# Power.net
KiCad netlist of a schematic drawn in Altium Designer
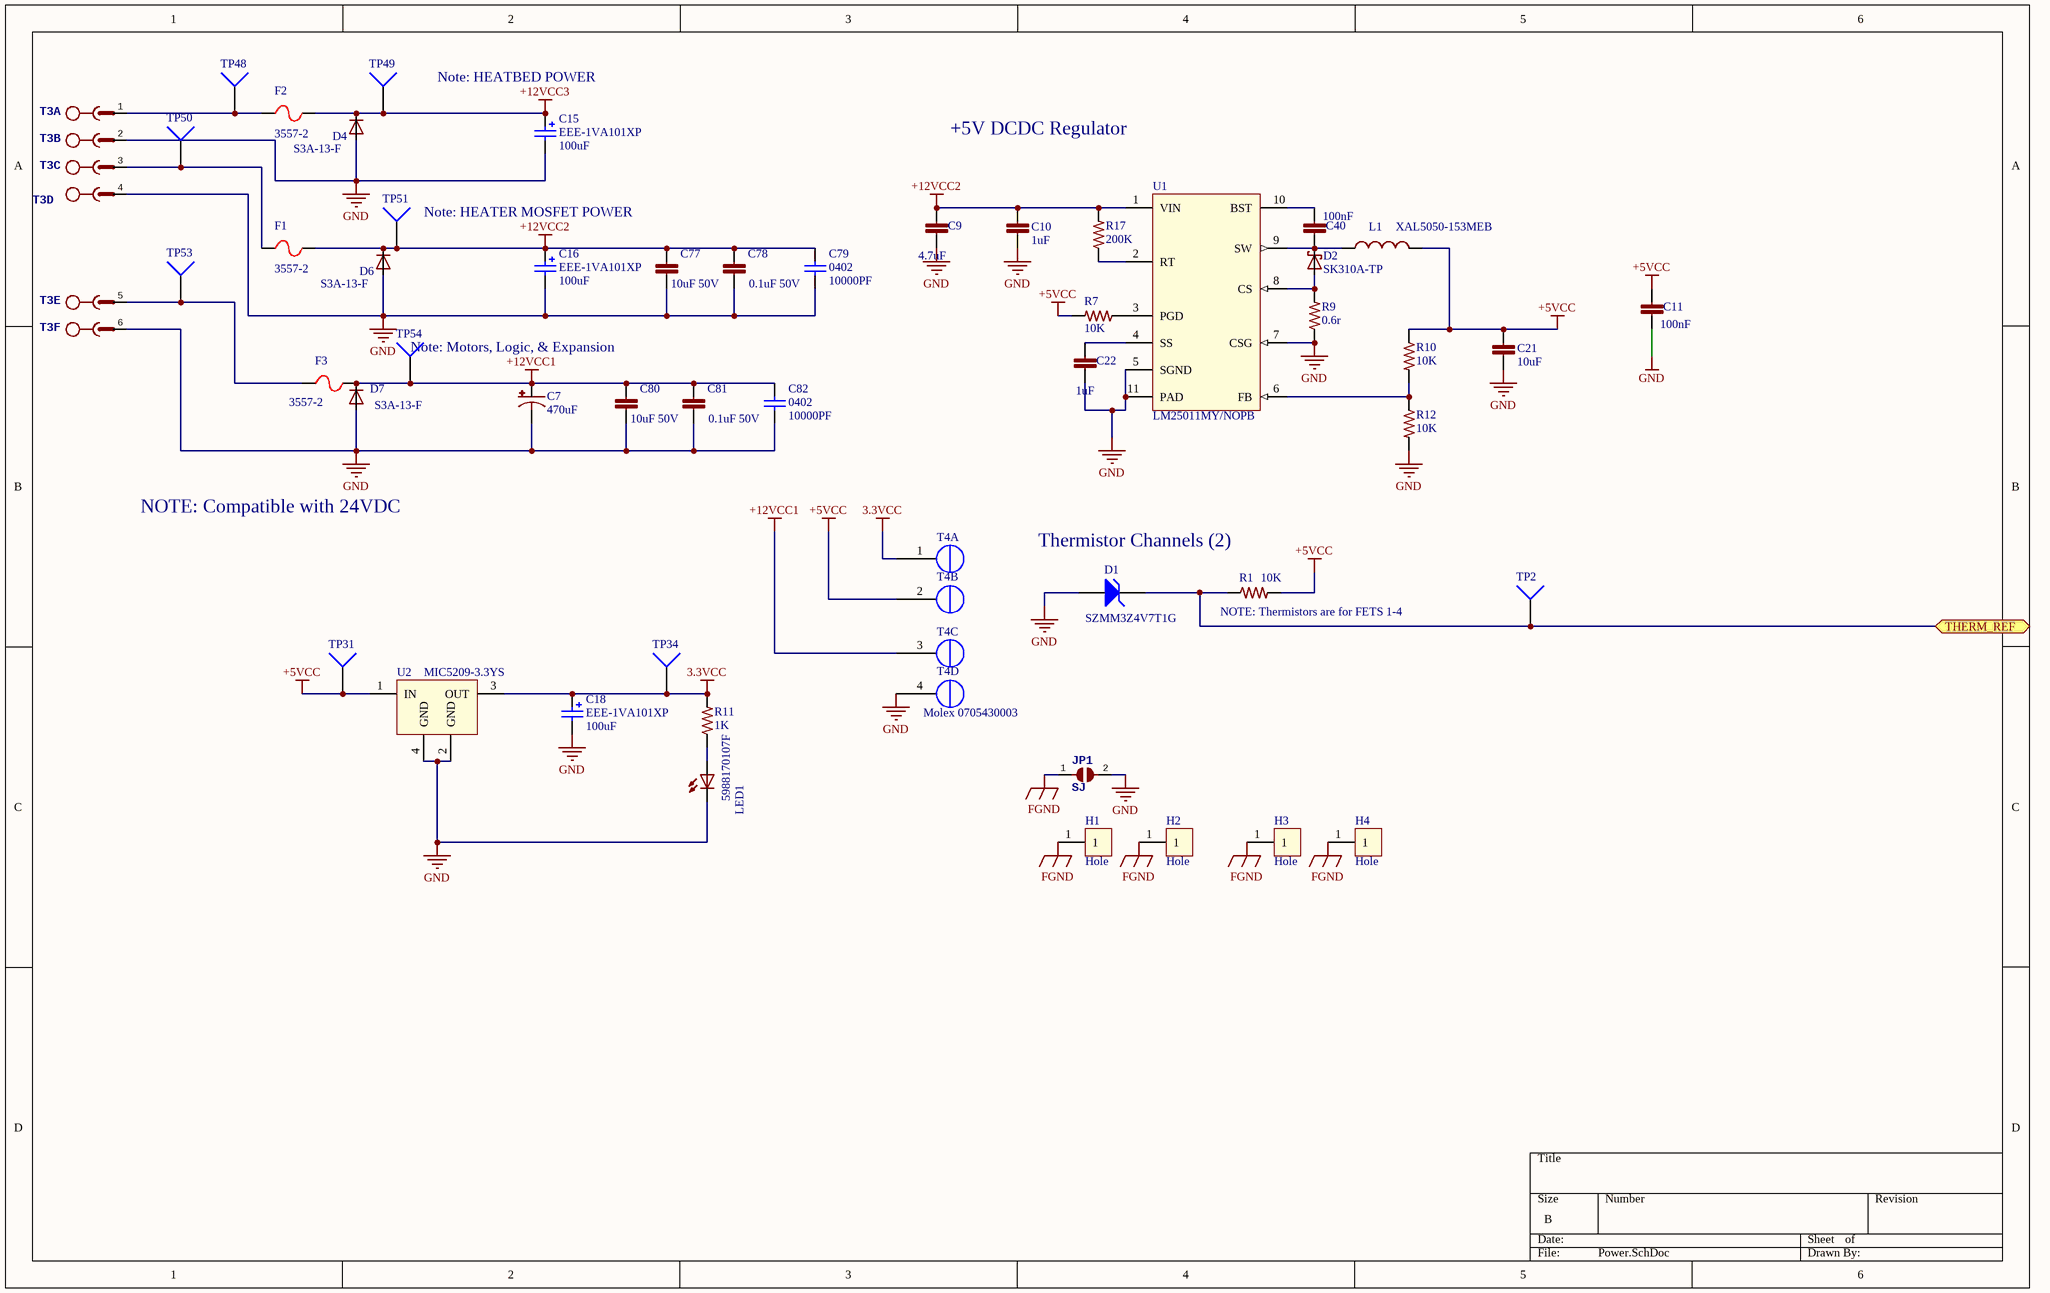
[diagram p0: Power.SchDoc]

(export (version "E")
  (design (tool "Eeschema 10.0.6"))
  (components
    (comp (ref "C7")
      (value "470uF")
      (footprint "C12,5-5")
      (description "CAP ALU 470uF 50V 20%")
      (fields
        (field (name "MANUFACTURERPARTNUMBER") "UPW1H471MHD1TO")
        (field (name "PUBLISHER") "UltiMachine")
      )
      (libsource (lib "Tigershark3D") (part "UPW1H471MHD1TO"))
    )
    (comp (ref "C9")
      (value "4.7uF")
      (footprint "C1206")
      (description "CAP CER 1206 4.7uF 50V 10% X5R")
      (fields
        (field (name "MANUFACTURERPARTNUMBER") "C1206C475K5PACTU")
        (field (name "PUBLISHER") "UltiMachine")
      )
      (libsource (lib "3Delight") (part "C1206C475K5PACTU"))
    )
    (comp (ref "C10")
      (value "1uF")
      (footprint "C0805")
      (description "CAP CER 0805 1uF 50V 10% X7R")
      (fields
        (field (name "MANUFACTURERPARTNUMBER") "GRM21BR71H105KA12L")
        (field (name "PUBLISHER") "UltiMachine")
      )
      (libsource (lib "3Delight") (part "GRM21BR71H105KA12L"))
    )
    (comp (ref "C11")
      (value "100nF")
      (footprint "C0603")
      (description "CAP CER 0603 100nF 50V 10% X7R")
      (fields
        (field (name "MANUFACTURERPARTNUMBER") "C0603C104K5RACTU")
        (field (name "PUBLISHER") "UltiMachine")
      )
      (libsource (lib "3Delight") (part "C0603C104K5RACTU"))
    )
    (comp (ref "C15")
      (value "EEE-1VA101XP")
      (footprint "EEE-1VA101XP")
      (description "CAP ALUM 100UF 35V 20% SMD")
      (fields (field (name "DIGIKEY PART #") "PCE3951CT-ND") (field (name "ALTIUM_VALUE") "100uF"))
      (libsource (lib "Tigershark3D") (part "EEE-1VA101XP"))
    )
    (comp (ref "C16")
      (value "EEE-1VA101XP")
      (footprint "EEE-1VA101XP")
      (description "CAP ALUM 100UF 35V 20% SMD")
      (fields (field (name "DIGIKEY PART #") "PCE3951CT-ND") (field (name "ALTIUM_VALUE") "100uF"))
      (libsource (lib "Tigershark3D") (part "EEE-1VA101XP"))
    )
    (comp (ref "C18")
      (value "EEE-1VA101XP")
      (footprint "EEE-1VA101XP")
      (description "CAP ALUM 100UF 35V 20% SMD")
      (fields (field (name "DIGIKEY PART #") "PCE3951CT-ND") (field (name "ALTIUM_VALUE") "100uF"))
      (libsource (lib "Tigershark3D") (part "EEE-1VA101XP"))
    )
    (comp (ref "C21")
      (value "10uF")
      (footprint "C0805")
      (description "CAP CER 0805 10uF 10V 10% X5R")
      (fields
        (field (name "MANUFACTURERPARTNUMBER") "C0805C106K8PACTU")
        (field (name "PUBLISHER") "UltiMachine")
      )
      (libsource (lib "3Delight") (part "C0805C106K8PACTU"))
    )
    (comp (ref "C22")
      (value "1uF")
      (footprint "C0402")
      (description "CAP CER 0402 1uF 6.3V 10% X5R")
      (fields
        (field (name "MANUFACTURERPARTNUMBER") "GRM155R60J105KE19D")
        (field (name "PUBLISHER") "UltiMachine")
      )
      (libsource (lib "3Delight") (part "GRM155R60J105KE19D"))
    )
    (comp (ref "C40")
      (value "100nF")
      (footprint "C0603")
      (description "CAP CER 0603 100nF 50V 10% X7R")
      (fields
        (field (name "MANUFACTURERPARTNUMBER") "C0603C104K5RACTU")
        (field (name "PUBLISHER") "UltiMachine")
      )
      (libsource (lib "3Delight") (part "C0603C104K5RACTU"))
    )
    (comp (ref "C77")
      (value "10uF 50V")
      (footprint "C1206")
      (description "CAP CER 10UF 50V 10% X5R 1206")
      (fields
        (field (name "MANUFACTURER") "Samsung")
        (field (name "MANUFACTURERPARTNUMBER") "CL31A106KBHNNNE")
        (field (name "PUBLISHER") "UltiMachine")
      )
      (libsource (lib "Tigershark3D") (part "CL31A106KBHNNNE"))
    )
    (comp (ref "C78")
      (value "0.1uF 50V")
      (footprint "C0603")
      (description "CAP CER 0.1UF 50V 10% X7R 0603")
      (fields
        (field (name "MANUFACTURERPARTNUMBER") "CL10B104KB8SFNC")
        (field (name "PUBLISHER") "UltiMachine")
      )
      (libsource (lib "Tigershark3D") (part "CL10B104KB8SFNC"))
    )
    (comp (ref "C79")
      (value "10000PF")
      (footprint "C0402")
      (description "CAP CER 10000PF 50V 5% X7R 0402")
      (fields
        (field (name "MANUFACTURE PART #") "CL05B103JB5NNNC")
        (field (name "MANUFACTURER") "Samsung")
        (field (name "PACKAGEREFERENCE") "0402")
        (field (name "PUBLISHER") "Ultimachine")
      )
      (libsource (lib "Tigershark3D") (part "CL05B103JB5NNNC"))
    )
    (comp (ref "C80")
      (value "10uF 50V")
      (footprint "C1206")
      (description "CAP CER 10UF 50V 10% X5R 1206")
      (fields
        (field (name "MANUFACTURER") "Samsung")
        (field (name "MANUFACTURERPARTNUMBER") "CL31A106KBHNNNE")
        (field (name "PUBLISHER") "UltiMachine")
      )
      (libsource (lib "Tigershark3D") (part "CL31A106KBHNNNE"))
    )
    (comp (ref "C81")
      (value "0.1uF 50V")
      (footprint "C0603")
      (description "CAP CER 0.1UF 50V 10% X7R 0603")
      (fields
        (field (name "MANUFACTURERPARTNUMBER") "CL10B104KB8SFNC")
        (field (name "PUBLISHER") "UltiMachine")
      )
      (libsource (lib "Tigershark3D") (part "CL10B104KB8SFNC"))
    )
    (comp (ref "C82")
      (value "10000PF")
      (footprint "C0402")
      (description "CAP CER 10000PF 50V 5% X7R 0402")
      (fields
        (field (name "MANUFACTURE PART #") "CL05B103JB5NNNC")
        (field (name "MANUFACTURER") "Samsung")
        (field (name "PACKAGEREFERENCE") "0402")
        (field (name "PUBLISHER") "Ultimachine")
      )
      (libsource (lib "Tigershark3D") (part "CL05B103JB5NNNC"))
    )
    (comp (ref "D1")
      (value "SZMM3Z4V7T1G")
      (footprint "SZMM3Z4V7T1G")
      (description "Zener Diode")
      (fields (field (name "PUBLISHER") "Altium Limited"))
      (libsource (lib "Miscellaneous Devices") (part "D Zener"))
    )
    (comp (ref "D2")
      (value "SK310A-TP")
      (footprint "SMA-SM")
      (description "DIODE Schottky 3A SMA")
      (fields (field (name "MANUFACTURERPARTNUMBER") "SK310A") (field (name "PUBLISHER") "UltiMachine"))
      (libsource (lib "3Delight") (part "SK310A"))
    )
    (comp (ref "D4")
      (value "S3A-13-F")
      (footprint "DO-214AB")
      (description "DIODE DO-214AB")
      (fields (field (name "PUBLISHER") "UltiMachine"))
      (libsource (lib "3Delight") (part "S3A-13-F"))
    )
    (comp (ref "D6")
      (value "S3A-13-F")
      (footprint "DO-214AB")
      (description "DIODE DO-214AB")
      (fields (field (name "PUBLISHER") "UltiMachine"))
      (libsource (lib "3Delight") (part "S3A-13-F"))
    )
    (comp (ref "D7")
      (value "S3A-13-F")
      (footprint "DO-214AB")
      (description "DIODE DO-214AB")
      (fields (field (name "PUBLISHER") "UltiMachine"))
      (libsource (lib "3Delight") (part "S3A-13-F"))
    )
    (comp (ref "F1")
      (value "3557-2")
      (footprint "3557")
      (description "FUSE PTH ATO")
      (fields (field (name "PUBLISHER") "UltiMachine"))
      (libsource (lib "3Delight") (part "3557-2"))
    )
    (comp (ref "F2")
      (value "3557-2")
      (footprint "3557")
      (description "FUSE PTH ATO")
      (fields (field (name "PUBLISHER") "UltiMachine"))
      (libsource (lib "3Delight") (part "3557-2"))
    )
    (comp (ref "F3")
      (value "3557-2")
      (footprint "3557")
      (description "FUSE PTH ATO")
      (fields (field (name "PUBLISHER") "UltiMachine"))
      (libsource (lib "3Delight") (part "3557-2"))
    )
    (comp (ref "H1")
      (value "Hole")
      (footprint "Wave_hole_3x7-singleSided")
      (libsource (lib "3Delight") (part "Hole"))
    )
    (comp (ref "H2")
      (value "Hole")
      (footprint "Wave_hole_3x7-singleSided")
      (libsource (lib "3Delight") (part "Hole"))
    )
    (comp (ref "H3")
      (value "Hole")
      (footprint "Wave_hole_3x7-singleSided")
      (libsource (lib "3Delight") (part "Hole"))
    )
    (comp (ref "H4")
      (value "Hole")
      (footprint "Wave_hole_3x7-singleSided")
      (libsource (lib "3Delight") (part "Hole"))
    )
    (comp (ref "JP1")
      (value "SJ")
      (footprint "SJ")
      (description "SMD solder jumper")
      (fields (field (name "PUBLISHER") "UltiMachine"))
      (libsource (lib "3Delight") (part "SJ"))
    )
    (comp (ref "L1")
      (value "XAL5050-153MEB")
      (footprint "XAL50xx-153")
      (description "IND 15uH 3.9A 20%")
      (fields (field (name "PUBLISHER") "UltiMachine"))
      (libsource (lib "3Delight") (part "XAL5050-153MEB"))
    )
    (comp (ref "LED1")
      (value "5988170107F")
      (footprint "LED2012120")
      (description "LED 0805 Green")
      (fields (field (name "PUBLISHER") "UltiMachine"))
      (libsource (lib "3Delight") (part "5988170107F"))
    )
    (comp (ref "R1")
      (value "10K")
      (footprint "R0603")
      (description "RES 0603 10K 100mW 1%")
      (fields
        (field (name "MANUFACTURERPARTNUMBER") "ERJ-3EKF1002V")
        (field (name "PUBLISHER") "UltiMachine")
      )
      (libsource (lib "3Delight") (part "ERJ-3EKF1002V"))
    )
    (comp (ref "R7")
      (value "10K")
      (footprint "R0603")
      (description "RES 0603 10K 100mW 1%")
      (fields
        (field (name "MANUFACTURERPARTNUMBER") "ERJ-3EKF1002V")
        (field (name "PUBLISHER") "UltiMachine")
      )
      (libsource (lib "3Delight") (part "ERJ-3EKF1002V"))
    )
    (comp (ref "R9")
      (value "0.6r")
      (footprint "2512R-0.55")
      (description "RES 0.06 OHM 1W 1% 2512 SMD")
      (fields
        (field (name "MANUFACTURERPARTNUMBER") "RL2512FK-070R06L")
        (field (name "PUBLISHER") "UltiMachine")
      )
      (libsource (lib "3Delight") (part "RL2512FK-070R06L"))
    )
    (comp (ref "R10")
      (value "10K")
      (footprint "R0603")
      (description "RES 0603 10K 100mW 1%")
      (fields
        (field (name "MANUFACTURERPARTNUMBER") "ERJ-3EKF1002V")
        (field (name "PUBLISHER") "UltiMachine")
      )
      (libsource (lib "3Delight") (part "ERJ-3EKF1002V"))
    )
    (comp (ref "R11")
      (value "1K")
      (footprint "R0603")
      (description "RES 0603 1K 100mW 1%")
      (fields
        (field (name "MANUFACTURERPARTNUMBER") "ERJ-3EKF1001V")
        (field (name "PUBLISHER") "UltiMachine")
      )
      (libsource (lib "Tigershark3D") (part "ERJ-3EKF1001V"))
    )
    (comp (ref "R12")
      (value "10K")
      (footprint "R0603")
      (description "RES 0603 10K 100mW 1%")
      (fields
        (field (name "MANUFACTURERPARTNUMBER") "ERJ-3EKF1002V")
        (field (name "PUBLISHER") "UltiMachine")
      )
      (libsource (lib "3Delight") (part "ERJ-3EKF1002V"))
    )
    (comp (ref "R17")
      (value "200K")
      (footprint "R0402")
      (description "RES 0402 22r 63mW 1%")
      (fields
        (field (name "MANUFACTURERPARTNUMBER") "CRCW0402200KFKED")
        (field (name "PUBLISHER") "UltiMachine")
      )
      (libsource (lib "3Delight") (part "CRCW0402200KFKED"))
    )
    (comp (ref "T3")
      (value "MSTBV6")
      (footprint "MSTBV6")
      (description "PHOENIX")
      (fields (field (name "PUBLISHER") "UltiMachine"))
      (libsource (lib "3Delight") (part "MSTBV6"))
    )
    (comp (ref "T4")
      (value "Molex 0705430003")
      (footprint "4POL254")
      (description "Molex 4 Pin Clip Connector")
      (libsource (lib "ZMBo Schematic Library") (part "Molex 0705430003 Alt"))
    )
    (comp (ref "TP2")
      (value "TP4")
      (footprint "TP-2")
      (description "Socket")
      (fields (field (name "PUBLISHER") "Altium Limited"))
      (libsource (lib "ZMBo Schematic Library") (part "Socket"))
    )
    (comp (ref "TP31")
      (value "TP4")
      (footprint "TP-2")
      (description "Socket")
      (fields (field (name "PUBLISHER") "Altium Limited"))
      (libsource (lib "ZMBo Schematic Library") (part "Socket"))
    )
    (comp (ref "TP34")
      (value "TP4")
      (footprint "TP-2")
      (description "Socket")
      (fields (field (name "PUBLISHER") "Altium Limited"))
      (libsource (lib "ZMBo Schematic Library") (part "Socket"))
    )
    (comp (ref "TP48")
      (value "TP4")
      (footprint "TP-2")
      (description "Socket")
      (fields (field (name "PUBLISHER") "Altium Limited"))
      (libsource (lib "ZMBo Schematic Library") (part "Socket"))
    )
    (comp (ref "TP49")
      (value "TP4")
      (footprint "TP-2")
      (description "Socket")
      (fields (field (name "PUBLISHER") "Altium Limited"))
      (libsource (lib "ZMBo Schematic Library") (part "Socket"))
    )
    (comp (ref "TP50")
      (value "TP4")
      (footprint "TP-2")
      (description "Socket")
      (fields (field (name "PUBLISHER") "Altium Limited"))
      (libsource (lib "ZMBo Schematic Library") (part "Socket"))
    )
    (comp (ref "TP51")
      (value "TP4")
      (footprint "TP-2")
      (description "Socket")
      (fields (field (name "PUBLISHER") "Altium Limited"))
      (libsource (lib "ZMBo Schematic Library") (part "Socket"))
    )
    (comp (ref "TP53")
      (value "TP4")
      (footprint "TP-2")
      (description "Socket")
      (fields (field (name "PUBLISHER") "Altium Limited"))
      (libsource (lib "ZMBo Schematic Library") (part "Socket"))
    )
    (comp (ref "TP54")
      (value "TP4")
      (footprint "TP-2")
      (description "Socket")
      (fields (field (name "PUBLISHER") "Altium Limited"))
      (libsource (lib "ZMBo Schematic Library") (part "Socket"))
    )
    (comp (ref "U1")
      (value "LM25011MY/NOPB")
      (footprint "VSSOP10")
      (description "REG BUCK")
      (libsource (lib "3Delight") (part "LM25011"))
    )
    (comp (ref "U2")
      (value "MIC5209-3.3YS")
      (footprint "SOT230P700X190-4N")
      (libsource (lib "3Delight") (part "MIC5209-3.3YS"))
    )
  )
  (nets
    (net (code "1") (name "+5VCC") (class "Default")
      (node (ref "C11") (pin "1") (pinfunction "1_1") (pintype "passive"))
      (node (ref "C21") (pin "1") (pinfunction "1_1") (pintype "passive"))
      (node (ref "L1") (pin "2") (pinfunction "2_2") (pintype "passive"))
      (node (ref "R1") (pin "2") (pinfunction "2_2") (pintype "passive"))
      (node (ref "R10") (pin "1") (pinfunction "1_1") (pintype "passive"))
      (node (ref "R7") (pin "2") (pinfunction "2_2") (pintype "passive"))
      (node (ref "T4") (pin "2") (pinfunction "OUT2A_2") (pintype "passive"))
      (node (ref "TP31") (pin "1") (pinfunction "1_1") (pintype "passive"))
      (node (ref "U2") (pin "1") (pinfunction "IN_1") (pintype "power_in"))
    )
    (net (code "2") (name "+12VCC1") (class "Default")
      (node (ref "C7") (pin "1") (pinfunction "+_1") (pintype "passive"))
      (node (ref "C80") (pin "1") (pinfunction "1_1") (pintype "passive"))
      (node (ref "C81") (pin "1") (pinfunction "1_1") (pintype "passive"))
      (node (ref "C82") (pin "2") (pinfunction "2_2") (pintype "passive"))
      (node (ref "D7") (pin "C") (pinfunction "C_C") (pintype "passive"))
      (node (ref "F3") (pin "2") (pinfunction "2_2") (pintype "passive"))
      (node (ref "T4") (pin "3") (pinfunction "OUT1A_3") (pintype "passive"))
      (node (ref "TP54") (pin "1") (pinfunction "1_1") (pintype "passive"))
    )
    (net (code "3") (name "+12VCC2") (class "Default")
      (node (ref "C10") (pin "1") (pinfunction "1_1") (pintype "passive"))
      (node (ref "C16") (pin "1") (pinfunction "1_1") (pintype "passive"))
      (node (ref "C77") (pin "1") (pinfunction "1_1") (pintype "passive"))
      (node (ref "C78") (pin "1") (pinfunction "1_1") (pintype "passive"))
      (node (ref "C79") (pin "2") (pinfunction "2_2") (pintype "passive"))
      (node (ref "C9") (pin "1") (pinfunction "1_1") (pintype "passive"))
      (node (ref "D6") (pin "C") (pinfunction "C_C") (pintype "passive"))
      (node (ref "F1") (pin "2") (pinfunction "2_2") (pintype "passive"))
      (node (ref "R17") (pin "2") (pinfunction "2_2") (pintype "passive"))
      (node (ref "TP51") (pin "1") (pinfunction "1_1") (pintype "passive"))
      (node (ref "U1") (pin "1") (pinfunction "VIN_1") (pintype "power_in"))
    )
    (net (code "4") (name "+12VCC3") (class "Default")
      (node (ref "C15") (pin "1") (pinfunction "1_1") (pintype "passive"))
      (node (ref "D4") (pin "C") (pinfunction "C_C") (pintype "passive"))
      (node (ref "F2") (pin "2") (pinfunction "2_2") (pintype "passive"))
      (node (ref "TP49") (pin "1") (pinfunction "1_1") (pintype "passive"))
    )
    (net (code "5") (name "/THERM_REF") (class "Default")
      (node (ref "D1") (pin "2") (pinfunction "K_2") (pintype "passive"))
      (node (ref "R1") (pin "1") (pinfunction "1_1") (pintype "passive"))
      (node (ref "TP2") (pin "1") (pinfunction "1_1") (pintype "passive"))
    )
    (net (code "6") (name "3.3VCC") (class "Default")
      (node (ref "C18") (pin "1") (pinfunction "1_1") (pintype "passive"))
      (node (ref "R11") (pin "2") (pinfunction "2_2") (pintype "passive"))
      (node (ref "T4") (pin "1") (pinfunction "OUT2B_1") (pintype "passive"))
      (node (ref "TP34") (pin "1") (pinfunction "1_1") (pintype "passive"))
      (node (ref "U2") (pin "3") (pinfunction "OUT_3") (pintype "power_in"))
    )
    (net (code "7") (name "FGND") (class "Default")
      (node (ref "H1") (pin "1") (pinfunction "1_1") (pintype "power_in"))
      (node (ref "H2") (pin "1") (pinfunction "1_1") (pintype "power_in"))
      (node (ref "H3") (pin "1") (pinfunction "1_1") (pintype "power_in"))
      (node (ref "H4") (pin "1") (pinfunction "1_1") (pintype "power_in"))
      (node (ref "JP1") (pin "1") (pinfunction "1_1") (pintype "passive"))
    )
    (net (code "8") (name "GND") (class "Default")
      (node (ref "C10") (pin "2") (pinfunction "2_2") (pintype "passive"))
      (node (ref "C11") (pin "2") (pinfunction "2_2") (pintype "passive"))
      (node (ref "C15") (pin "2") (pinfunction "2_2") (pintype "passive"))
      (node (ref "C16") (pin "2") (pinfunction "2_2") (pintype "passive"))
      (node (ref "C18") (pin "2") (pinfunction "2_2") (pintype "passive"))
      (node (ref "C21") (pin "2") (pinfunction "2_2") (pintype "passive"))
      (node (ref "C22") (pin "2") (pinfunction "2_2") (pintype "passive"))
      (node (ref "C7") (pin "2") (pinfunction "-_2") (pintype "passive"))
      (node (ref "C77") (pin "2") (pinfunction "2_2") (pintype "passive"))
      (node (ref "C78") (pin "2") (pinfunction "2_2") (pintype "passive"))
      (node (ref "C79") (pin "1") (pinfunction "1_1") (pintype "passive"))
      (node (ref "C80") (pin "2") (pinfunction "2_2") (pintype "passive"))
      (node (ref "C81") (pin "2") (pinfunction "2_2") (pintype "passive"))
      (node (ref "C82") (pin "1") (pinfunction "1_1") (pintype "passive"))
      (node (ref "C9") (pin "2") (pinfunction "2_2") (pintype "passive"))
      (node (ref "D1") (pin "1") (pinfunction "A_1") (pintype "passive"))
      (node (ref "D4") (pin "A") (pinfunction "A_A") (pintype "passive"))
      (node (ref "D6") (pin "A") (pinfunction "A_A") (pintype "passive"))
      (node (ref "D7") (pin "A") (pinfunction "A_A") (pintype "passive"))
      (node (ref "JP1") (pin "2") (pinfunction "2_2") (pintype "passive"))
      (node (ref "LED1") (pin "C") (pinfunction "C_C") (pintype "passive"))
      (node (ref "R12") (pin "2") (pinfunction "2_2") (pintype "passive"))
      (node (ref "R9") (pin "1") (pinfunction "1_1") (pintype "passive"))
      (node (ref "T3") (pin "2") (pinfunction "1_2") (pintype "passive"))
      (node (ref "T3") (pin "4") (pinfunction "1_4") (pintype "passive"))
      (node (ref "T3") (pin "6") (pinfunction "1_6") (pintype "passive"))
      (node (ref "T4") (pin "4") (pinfunction "OUT1B_4") (pintype "passive"))
      (node (ref "U1") (pin "11") (pinfunction "PAD_11") (pintype "power_in"))
      (node (ref "U1") (pin "5") (pinfunction "SGND_5") (pintype "power_in"))
      (node (ref "U1") (pin "7") (pinfunction "CSG_7") (pintype "input"))
      (node (ref "U2") (pin "2") (pinfunction "GND_2") (pintype "power_in"))
      (node (ref "U2") (pin "4") (pinfunction "GND_4") (pintype "power_in"))
    )
    (net (code "9") (name "Net-(F2-Pad1)") (class "Default")
      (node (ref "F2") (pin "1") (pinfunction "1_1") (pintype "passive"))
      (node (ref "T3") (pin "1") (pinfunction "1_1") (pintype "passive"))
      (node (ref "TP48") (pin "1") (pinfunction "1_1") (pintype "passive"))
    )
    (net (code "10") (name "Net-(LED1-PadA)") (class "Default")
      (node (ref "LED1") (pin "A") (pinfunction "A_A") (pintype "passive"))
      (node (ref "R11") (pin "1") (pinfunction "1_1") (pintype "passive"))
    )
    (net (code "11") (name "Net-(T3C-1)") (class "Default")
      (node (ref "F1") (pin "1") (pinfunction "1_1") (pintype "passive"))
      (node (ref "T3") (pin "3") (pinfunction "1_3") (pintype "passive"))
      (node (ref "TP50") (pin "1") (pinfunction "1_1") (pintype "passive"))
    )
    (net (code "12") (name "Net-(T3E-1)") (class "Default")
      (node (ref "F3") (pin "1") (pinfunction "1_1") (pintype "passive"))
      (node (ref "T3") (pin "5") (pinfunction "1_5") (pintype "passive"))
      (node (ref "TP53") (pin "1") (pinfunction "1_1") (pintype "passive"))
    )
    (net (code "13") (name "Net-(U1-BST)") (class "Default")
      (node (ref "C40") (pin "1") (pinfunction "1_1") (pintype "passive"))
      (node (ref "U1") (pin "10") (pinfunction "BST_10") (pintype "power_in"))
    )
    (net (code "14") (name "Net-(U1-CS)") (class "Default")
      (node (ref "D2") (pin "A") (pinfunction "A_A") (pintype "passive"))
      (node (ref "R9") (pin "2") (pinfunction "2_2") (pintype "passive"))
      (node (ref "U1") (pin "8") (pinfunction "CS_8") (pintype "input"))
    )
    (net (code "15") (name "Net-(U1-FB)") (class "Default")
      (node (ref "R10") (pin "2") (pinfunction "2_2") (pintype "passive"))
      (node (ref "R12") (pin "1") (pinfunction "1_1") (pintype "passive"))
      (node (ref "U1") (pin "6") (pinfunction "FB_6") (pintype "input"))
    )
    (net (code "16") (name "Net-(U1-PGD)") (class "Default")
      (node (ref "R7") (pin "1") (pinfunction "1_1") (pintype "passive"))
      (node (ref "U1") (pin "3") (pinfunction "PGD_3") (pintype "power_in"))
    )
    (net (code "17") (name "Net-(U1-RT)") (class "Default")
      (node (ref "R17") (pin "1") (pinfunction "1_1") (pintype "passive"))
      (node (ref "U1") (pin "2") (pinfunction "RT_2") (pintype "power_in"))
    )
    (net (code "18") (name "Net-(U1-SS)") (class "Default")
      (node (ref "C22") (pin "1") (pinfunction "1_1") (pintype "passive"))
      (node (ref "U1") (pin "4") (pinfunction "SS_4") (pintype "power_in"))
    )
    (net (code "19") (name "Net-(U1-SW)") (class "Default")
      (node (ref "C40") (pin "2") (pinfunction "2_2") (pintype "passive"))
      (node (ref "D2") (pin "C") (pinfunction "C_C") (pintype "passive"))
      (node (ref "L1") (pin "1") (pinfunction "1_1") (pintype "passive"))
      (node (ref "U1") (pin "9") (pinfunction "SW_9") (pintype "output"))
    )
  )
)
